# OpenBeacon.net
KiCad netlist of a schematic drawn in Altium Designer
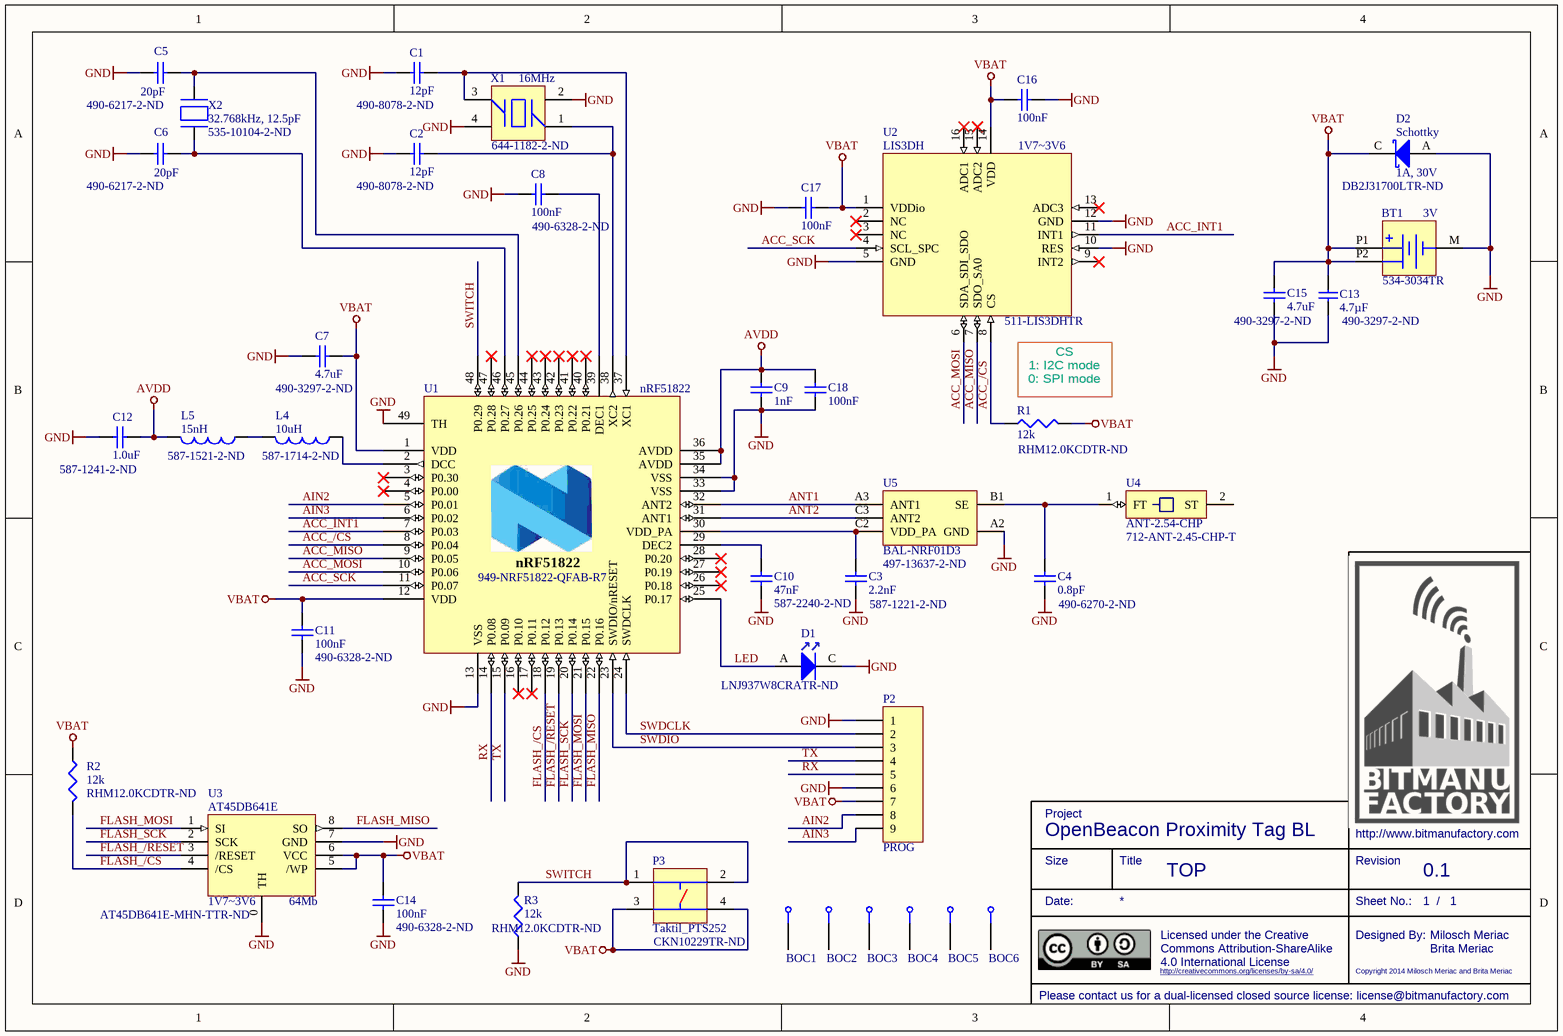
[diagram p0: OpenBeacon.SchDoc]

(export (version "E")
  (design (tool "Eeschema 10.0.6"))
  (components
    (comp (ref "BOC1")
      (value "Testpad")
      (footprint "TESTPAD_1MM")
      (libsource (lib "Bitmanufaktur") (part "Testpad"))
    )
    (comp (ref "BOC2")
      (value "Testpad")
      (footprint "TESTPAD_1MM")
      (libsource (lib "Bitmanufaktur") (part "Testpad"))
    )
    (comp (ref "BOC3")
      (value "Testpad")
      (footprint "TESTPAD_1MM")
      (libsource (lib "Bitmanufaktur") (part "Testpad"))
    )
    (comp (ref "BOC4")
      (value "Testpad")
      (footprint "TESTPAD_1MM")
      (libsource (lib "Bitmanufaktur") (part "Testpad"))
    )
    (comp (ref "BOC5")
      (value "Testpad")
      (footprint "TESTPAD_1MM")
      (libsource (lib "Bitmanufaktur") (part "Testpad"))
    )
    (comp (ref "BOC6")
      (value "Testpad")
      (footprint "TESTPAD_1MM")
      (libsource (lib "Bitmanufaktur") (part "Testpad"))
    )
    (comp (ref "BT1")
      (value "3V")
      (footprint "BAT-Holder_3034")
      (description "Battery Cell")
      (fields
        (field (name "SUPPLIER PART NUMBER 1") "534-3034TR")
        (field (name "Comment") "Battery Cell Holder")
      )
      (libsource (lib "Bitmanufaktur") (part "Battery_Cell"))
    )
    (comp (ref "C1")
      (value "12pF")
      (footprint "0402[1005]")
      (description "Capacitor (Semiconductor SIM Model)")
      (fields (field (name "TOLERANCE") "2%, NPO") (field (name "SUPPLIER PART NUMBER 1") "490-8078-2-ND"))
      (libsource (lib "Miscellaneous Devices") (part "Cap Semi"))
    )
    (comp (ref "C2")
      (value "12pF")
      (footprint "0402[1005]")
      (description "Capacitor (Semiconductor SIM Model)")
      (fields (field (name "TOLERANCE") "2%, NPO") (field (name "SUPPLIER PART NUMBER 1") "490-8078-2-ND"))
      (libsource (lib "Miscellaneous Devices") (part "Cap Semi"))
    )
    (comp (ref "C3")
      (value "2.2nF")
      (footprint "0402[1005]")
      (description "Capacitor (Semiconductor SIM Model)")
      (fields (field (name "TOLERANCE") "X7R, ±10%") (field (name "SUPPLIER PART NUMBER 1") "587-1221-2-ND"))
      (libsource (lib "Miscellaneous Devices") (part "Cap Semi"))
    )
    (comp (ref "C4")
      (value "0.8pF")
      (footprint "0402[1005]")
      (description "Capacitor (Semiconductor SIM Model)")
      (fields (field (name "TOLERANCE") "NP0, ±5%") (field (name "SUPPLIER PART NUMBER 1") "490-6270-2-ND"))
      (libsource (lib "Miscellaneous Devices") (part "Cap Semi"))
    )
    (comp (ref "C5")
      (value "20pF")
      (footprint "0402[1005]")
      (description "Capacitor (Semiconductor SIM Model)")
      (fields (field (name "SUPPLIER PART NUMBER 1") "490-6217-2-ND") (field (name "Comment") "Cap 20pF"))
      (libsource (lib "Bitmanufaktur") (part "Cap Semi"))
    )
    (comp (ref "C6")
      (value "20pF")
      (footprint "0402[1005]")
      (description "Capacitor (Semiconductor SIM Model)")
      (fields (field (name "SUPPLIER PART NUMBER 1") "490-6217-2-ND") (field (name "Comment") "Cap 20pF"))
      (libsource (lib "Bitmanufaktur") (part "Cap Semi"))
    )
    (comp (ref "C7")
      (value "4.7uF")
      (footprint "0603[1608]_a")
      (description "Capacitor (Semiconductor SIM Model)")
      (fields (field (name "TOLERANCE") "X5R, ±10%") (field (name "SUPPLIER PART NUMBER 1") "490-3297-2-ND"))
      (libsource (lib "Miscellaneous Devices") (part "Cap Semi"))
    )
    (comp (ref "C8")
      (value "100nF")
      (footprint "0402[1005]")
      (description "Capacitor (Semiconductor SIM Model)")
      (fields (field (name "TOLERANCE") "10%, X7R") (field (name "SUPPLIER PART NUMBER 1") "490-6328-2-ND"))
      (libsource (lib "Miscellaneous Devices") (part "Cap Semi"))
    )
    (comp (ref "C9")
      (value "1nF")
      (footprint "0402[1005]")
      (description "Capacitor (Semiconductor SIM Model)")
      (fields (field (name "TOLERANCE") "X7R, ±10%"))
      (libsource (lib "Miscellaneous Devices") (part "Cap Semi"))
    )
    (comp (ref "C10")
      (value "47nF")
      (footprint "0402[1005]")
      (description "Capacitor (Semiconductor SIM Model)")
      (fields (field (name "TOLERANCE") "X7R, ±10%") (field (name "SUPPLIER PART NUMBER 1") "587-2240-2-ND"))
      (libsource (lib "Miscellaneous Devices") (part "Cap Semi"))
    )
    (comp (ref "C11")
      (value "100nF")
      (footprint "0402[1005]")
      (description "Capacitor (Semiconductor SIM Model)")
      (fields (field (name "TOLERANCE") "10%, X7R") (field (name "SUPPLIER PART NUMBER 1") "490-6328-2-ND"))
      (libsource (lib "Miscellaneous Devices") (part "Cap Semi"))
    )
    (comp (ref "C12")
      (value "1.0uF")
      (footprint "0603[1608]_a")
      (description "Capacitor (Semiconductor SIM Model)")
      (fields (field (name "TOLERANCE") "10%, X7R") (field (name "SUPPLIER PART NUMBER 1") "587-1241-2-ND"))
      (libsource (lib "Miscellaneous Devices") (part "Cap Semi"))
    )
    (comp (ref "C13")
      (value "4.7µF")
      (footprint "0603[1608]_a")
      (description "Capacitor, X5R, ±10%")
      (fields
        (field (name "PART NUMBER") "C0603-4µ7")
        (field (name "SUPPLIER PART NUMBER 1") "490-3297-2-ND")
        (field (name "PUBLISHER") "Nordic Semiconductor")
      )
      (libsource (lib "Nordic Passive DB") (part "CAP"))
    )
    (comp (ref "C14")
      (value "100nF")
      (footprint "0402[1005]")
      (description "Capacitor (Semiconductor SIM Model)")
      (fields (field (name "TOLERANCE") "10%, X7R") (field (name "SUPPLIER PART NUMBER 1") "490-6328-2-ND"))
      (libsource (lib "Miscellaneous Devices") (part "Cap Semi"))
    )
    (comp (ref "C15")
      (value "4.7uF")
      (footprint "0603[1608]_a")
      (description "Capacitor (Semiconductor SIM Model)")
      (fields (field (name "TOLERANCE") "X5R, ±10%") (field (name "SUPPLIER PART NUMBER 1") "490-3297-2-ND"))
      (libsource (lib "Miscellaneous Devices") (part "Cap Semi"))
    )
    (comp (ref "C16")
      (value "100nF")
      (footprint "0402[1005]")
      (description "Capacitor (Semiconductor SIM Model)")
      (fields (field (name "TOLERANCE") "10%, X7R"))
      (libsource (lib "Miscellaneous Devices") (part "Cap Semi"))
    )
    (comp (ref "C17")
      (value "100nF")
      (footprint "0402[1005]")
      (description "Capacitor (Semiconductor SIM Model)")
      (fields (field (name "TOLERANCE") "10%, X7R"))
      (libsource (lib "Miscellaneous Devices") (part "Cap Semi"))
    )
    (comp (ref "C18")
      (value "100nF")
      (footprint "0402[1005]")
      (description "Capacitor (Semiconductor SIM Model)")
      (fields (field (name "TOLERANCE") "10%, X7R"))
      (libsource (lib "Miscellaneous Devices") (part "Cap Semi"))
    )
    (comp (ref "D1")
      (value "LED blue")
      (footprint "LED_0603")
      (description "LED")
      (fields (field (name "SUPPLIER PART NUMBER 1") "LNJ937W8CRATR-ND"))
      (libsource (lib "Bitmanufaktur") (part "LED"))
    )
    (comp (ref "D2")
      (value "Schottky")
      (footprint "SC-90A")
      (description "Schottky barrier diode")
      (fields
        (field (name "ALTIUM_VALUE") "1A, 30V")
        (field (name "SUPPLIER PART NUMBER 1") "DB2J31700LTR-ND")
      )
      (libsource (lib "Bitmanufaktur") (part "Diode_Shottky"))
    )
    (comp (ref "L4")
      (value "10uH")
      (footprint "0603[1608]_a")
      (description "Inductor / Spule")
      (fields (field (name "TOLERANCE") "10%") (field (name "SUPPLIER PART NUMBER 1") "587-1714-2-ND"))
      (libsource (lib "Bitmanufaktur") (part "COIL"))
    )
    (comp (ref "L5")
      (value "15nH")
      (footprint "0402[1005]")
      (description "Inductor / Spule")
      (fields (field (name "TOLERANCE") "5%") (field (name "SUPPLIER PART NUMBER 1") "587-1521-2-ND"))
      (libsource (lib "Bitmanufaktur") (part "COIL"))
    )
    (comp (ref "P2")
      (value "PROG")
      (footprint "HDR1X9_round_custom-SMD")
      (description "Header, 9-Pin")
      (libsource (lib "Miscellaneous Connectors") (part "Header 9"))
    )
    (comp (ref "P3")
      (value "Taktil_PTS252")
      (footprint "taktil_PTS525")
      (description "Taster")
      (fields (field (name "SUPPLIER PART NUMBER 1") "CKN10229TR-ND"))
      (libsource (lib "Bitmanufaktur") (part "Taktil_PTS252"))
    )
    (comp (ref "R1")
      (value "12k")
      (footprint "0402[1005]")
      (description "Resistor")
      (fields (field (name "TOLERANCE") "1%") (field (name "SUPPLIER PART NUMBER 1") "RHM12.0KCDTR-ND"))
      (libsource (lib "Bitmanufaktur") (part "Res"))
    )
    (comp (ref "R2")
      (value "12k")
      (footprint "0402[1005]")
      (description "Resistor")
      (fields (field (name "TOLERANCE") "1%") (field (name "SUPPLIER PART NUMBER 1") "RHM12.0KCDTR-ND"))
      (libsource (lib "Bitmanufaktur") (part "Res"))
    )
    (comp (ref "R3")
      (value "12k")
      (footprint "0402[1005]")
      (description "Resistor")
      (fields (field (name "TOLERANCE") "1%") (field (name "SUPPLIER PART NUMBER 1") "RHM12.0KCDTR-ND"))
      (libsource (lib "Bitmanufaktur") (part "Res"))
    )
    (comp (ref "U1")
      (value "nRF51822")
      (footprint "QFN-48")
      (fields (field (name "SUPPLIER PART NUMBER 1") "949-NRF51822-QFAB-R7"))
      (libsource (lib "Bitmanufaktur") (part "nRF51822"))
    )
    (comp (ref "U2")
      (value "LIS3DH")
      (footprint "LGA-16")
      (description "LIS3DH, MEMS digital output motion sensor")
      (fields
        (field (name "SUPPLY VOLTAGE") "1V7~3V6")
        (field (name "SUPPLIER PART NUMBER 1") "511-LIS3DHTR")
      )
      (libsource (lib "Bitmanufaktur") (part "LIS3DH"))
    )
    (comp (ref "U3")
      (value "AT45DB641E")
      (footprint "UDFN-8MA1")
      (description "serial interface Flash memory (1.7V-3.6V)")
      (fields
        (field (name "ALTIUM_VALUE") "64Mb")
        (field (name "SUPPLY VOLTAGE") "1V7~3V6")
        (field (name "SUPPLIER PART NUMBER 1") "AT45DB641E-MHN-TTR-ND")
      )
      (libsource (lib "Bitmanufaktur") (part "AT45DB641E"))
    )
    (comp (ref "U4")
      (value "ANT-2.54-CHP")
      (footprint "ANT-CHP_rainsun")
      (description "ANT-2.54-CHP, 2.45GHz Ultra-Compact Chip Antenna")
      (fields (field (name "SUPPLIER PART NUMBER 1") "712-ANT-2.45-CHP-T"))
      (libsource (lib "Bitmanufaktur") (part "ANT-CHP"))
    )
    (comp (ref "U5")
      (value "BAL-NRF01D3")
      (footprint "BAL-NRF01D3")
      (description "ST BAL-NRF01D31")
      (fields (field (name "SUPPLIER PART NUMBER 1") "497-13637-2-ND"))
      (libsource (lib "Bitmanufaktur") (part "BAL-NRF01D3"))
    )
    (comp (ref "X1")
      (value "16MHz")
      (footprint "SMD3225")
      (description "ABM8 ceramic crystal")
      (fields (field (name "SUPPLIER PART NUMBER 1") "644-1182-2-ND") (field (name "Comment") "XTAL_4Pin"))
      (libsource (lib "Bitmanufaktur") (part "XTAL_4Pin"))
    )
    (comp (ref "X2")
      (value "32.768kHz, 12.5pF")
      (footprint "ABS06")
      (description "Crystal")
      (fields (field (name "SUPPLIER PART NUMBER 1") "535-10104-2-ND") (field (name "Comment") "XTAL-2pin"))
      (libsource (lib "Bitmanufaktur") (part "XTAL_2Pin"))
    )
  )
  (nets
    (net (code "1") (name "/ACC_INT1") (class "Default")
      (node (ref "U1") (pin "7") (pinfunction "P0.03_7") (pintype "bidirectional"))
      (node (ref "U2") (pin "11") (pinfunction "INT1_11") (pintype "output"))
    )
    (net (code "2") (name "/ACC_MISO") (class "Default")
      (node (ref "U1") (pin "9") (pinfunction "P0.05_9") (pintype "bidirectional"))
      (node (ref "U2") (pin "7") (pinfunction "SDO_SA0_7") (pintype "bidirectional"))
    )
    (net (code "3") (name "/ACC_MOSI") (class "Default")
      (node (ref "U1") (pin "10") (pinfunction "P0.06_10") (pintype "bidirectional"))
      (node (ref "U2") (pin "6") (pinfunction "SDA_SDI_SDO_6") (pintype "bidirectional"))
    )
    (net (code "4") (name "/ACC_SCK") (class "Default")
      (node (ref "U1") (pin "11") (pinfunction "P0.07_11") (pintype "bidirectional"))
      (node (ref "U2") (pin "4") (pinfunction "SCL_SPC_4") (pintype "input"))
    )
    (net (code "5") (name "/ACC_{slash}CS") (class "Default")
      (node (ref "R1") (pin "1") (pinfunction "1_1") (pintype "passive"))
      (node (ref "U1") (pin "8") (pinfunction "P0.04_8") (pintype "bidirectional"))
      (node (ref "U2") (pin "8") (pinfunction "CS_8") (pintype "input"))
    )
    (net (code "6") (name "/AIN2") (class "Default")
      (node (ref "P2") (pin "8") (pinfunction "8_8") (pintype "passive"))
      (node (ref "U1") (pin "5") (pinfunction "P0.01_5") (pintype "bidirectional"))
    )
    (net (code "7") (name "/AIN3") (class "Default")
      (node (ref "P2") (pin "9") (pinfunction "9_9") (pintype "passive"))
      (node (ref "U1") (pin "6") (pinfunction "P0.02_6") (pintype "bidirectional"))
    )
    (net (code "8") (name "/ANT1") (class "Default")
      (node (ref "U1") (pin "32") (pinfunction "ANT2_32") (pintype "bidirectional"))
      (node (ref "U5") (pin "A3") (pinfunction "ANT1_A3") (pintype "passive"))
    )
    (net (code "9") (name "/ANT2") (class "Default")
      (node (ref "U1") (pin "31") (pinfunction "ANT1_31") (pintype "bidirectional"))
      (node (ref "U5") (pin "C3") (pinfunction "ANT2_C3") (pintype "passive"))
    )
    (net (code "10") (name "/FLASH_MISO") (class "Default")
      (node (ref "U1") (pin "22") (pinfunction "P0.16_22") (pintype "bidirectional"))
      (node (ref "U3") (pin "8") (pinfunction "SO_8") (pintype "output"))
    )
    (net (code "11") (name "/FLASH_MOSI") (class "Default")
      (node (ref "U1") (pin "21") (pinfunction "P0.15_21") (pintype "bidirectional"))
      (node (ref "U3") (pin "1") (pinfunction "SI_1") (pintype "input"))
    )
    (net (code "12") (name "/FLASH_SCK") (class "Default")
      (node (ref "U1") (pin "20") (pinfunction "P0.14_20") (pintype "bidirectional"))
      (node (ref "U3") (pin "2") (pinfunction "SCK_2") (pintype "passive"))
    )
    (net (code "13") (name "/FLASH_{slash}CS") (class "Default")
      (node (ref "R2") (pin "2") (pinfunction "2_2") (pintype "passive"))
      (node (ref "U1") (pin "18") (pinfunction "P0.12_18") (pintype "bidirectional"))
      (node (ref "U3") (pin "4") (pinfunction "/CS_4") (pintype "passive"))
    )
    (net (code "14") (name "/FLASH_{slash}RESET") (class "Default")
      (node (ref "U1") (pin "19") (pinfunction "P0.13_19") (pintype "bidirectional"))
      (node (ref "U3") (pin "3") (pinfunction "/RESET_3") (pintype "passive"))
    )
    (net (code "15") (name "/LED") (class "Default")
      (node (ref "D1") (pin "A") (pinfunction "Anode_A") (pintype "passive"))
      (node (ref "U1") (pin "25") (pinfunction "P0.17_25") (pintype "bidirectional"))
    )
    (net (code "16") (name "/RX") (class "Default")
      (node (ref "P2") (pin "5") (pinfunction "5_5") (pintype "passive"))
      (node (ref "U1") (pin "14") (pinfunction "P0.08_14") (pintype "bidirectional"))
    )
    (net (code "17") (name "/SWDCLK") (class "Default")
      (node (ref "P2") (pin "2") (pinfunction "2_2") (pintype "passive"))
      (node (ref "U1") (pin "24") (pinfunction "SWDCLK_24") (pintype "input"))
    )
    (net (code "18") (name "/SWDIO") (class "Default")
      (node (ref "P2") (pin "3") (pinfunction "3_3") (pintype "passive"))
      (node (ref "U1") (pin "23") (pinfunction "SWDIO/nRESET_23") (pintype "input"))
    )
    (net (code "19") (name "/SWITCH") (class "Default")
      (node (ref "P3") (pin "1") (pintype "passive"))
      (node (ref "P3") (pin "2") (pintype "passive"))
      (node (ref "R3") (pin "1") (pinfunction "1_1") (pintype "passive"))
      (node (ref "U1") (pin "48") (pinfunction "P0.29_48") (pintype "bidirectional"))
    )
    (net (code "20") (name "/TX") (class "Default")
      (node (ref "P2") (pin "4") (pinfunction "4_4") (pintype "passive"))
      (node (ref "U1") (pin "15") (pinfunction "P0.09_15") (pintype "bidirectional"))
    )
    (net (code "21") (name "AVDD") (class "Default")
      (node (ref "C12") (pin "1") (pinfunction "1_1") (pintype "passive"))
      (node (ref "C18") (pin "1") (pinfunction "1_1") (pintype "passive"))
      (node (ref "C9") (pin "1") (pinfunction "1_1") (pintype "passive"))
      (node (ref "L5") (pin "2") (pinfunction "2_2") (pintype "passive"))
      (node (ref "U1") (pin "35") (pinfunction "AVDD_35") (pintype "power_in"))
      (node (ref "U1") (pin "36") (pinfunction "AVDD_36") (pintype "power_in"))
    )
    (net (code "22") (name "GND") (class "Default")
      (node (ref "BT1") (pin "M") (pinfunction "M_M") (pintype "power_in"))
      (node (ref "C1") (pin "2") (pinfunction "2_2") (pintype "passive"))
      (node (ref "C10") (pin "2") (pinfunction "2_2") (pintype "passive"))
      (node (ref "C11") (pin "2") (pinfunction "2_2") (pintype "passive"))
      (node (ref "C12") (pin "2") (pinfunction "2_2") (pintype "passive"))
      (node (ref "C13") (pin "1") (pinfunction "1_1") (pintype "passive"))
      (node (ref "C14") (pin "2") (pinfunction "2_2") (pintype "passive"))
      (node (ref "C15") (pin "2") (pinfunction "2_2") (pintype "passive"))
      (node (ref "C16") (pin "1") (pinfunction "1_1") (pintype "passive"))
      (node (ref "C17") (pin "2") (pinfunction "2_2") (pintype "passive"))
      (node (ref "C18") (pin "2") (pinfunction "2_2") (pintype "passive"))
      (node (ref "C2") (pin "2") (pinfunction "2_2") (pintype "passive"))
      (node (ref "C3") (pin "2") (pinfunction "2_2") (pintype "passive"))
      (node (ref "C4") (pin "2") (pinfunction "2_2") (pintype "passive"))
      (node (ref "C5") (pin "1") (pinfunction "1_1") (pintype "passive"))
      (node (ref "C6") (pin "1") (pinfunction "1_1") (pintype "passive"))
      (node (ref "C7") (pin "2") (pinfunction "2_2") (pintype "passive"))
      (node (ref "C8") (pin "2") (pinfunction "2_2") (pintype "passive"))
      (node (ref "C9") (pin "2") (pinfunction "2_2") (pintype "passive"))
      (node (ref "D1") (pin "C") (pinfunction "Cathode_C") (pintype "passive"))
      (node (ref "D2") (pin "A") (pinfunction "Anode_A") (pintype "passive"))
      (node (ref "P2") (pin "1") (pinfunction "1_1") (pintype "passive"))
      (node (ref "P2") (pin "6") (pinfunction "6_6") (pintype "passive"))
      (node (ref "R3") (pin "2") (pinfunction "2_2") (pintype "passive"))
      (node (ref "U1") (pin "13") (pinfunction "VSS_13") (pintype "power_in"))
      (node (ref "U1") (pin "33") (pinfunction "VSS_33") (pintype "power_in"))
      (node (ref "U1") (pin "34") (pinfunction "VSS_34") (pintype "power_in"))
      (node (ref "U1") (pin "49") (pinfunction "TH_49") (pintype "passive"))
      (node (ref "U2") (pin "10") (pinfunction "RES_10") (pintype "input"))
      (node (ref "U2") (pin "12") (pinfunction "GND_12") (pintype "power_in"))
      (node (ref "U2") (pin "5") (pinfunction "GND_5") (pintype "power_in"))
      (node (ref "U3") (pin "0") (pinfunction "TH_0") (pintype "passive"))
      (node (ref "U3") (pin "7") (pinfunction "GND_7") (pintype "power_in"))
      (node (ref "U5") (pin "A2") (pinfunction "GND_A2") (pintype "passive"))
      (node (ref "X1") (pin "2") (pintype "passive"))
      (node (ref "X1") (pin "4") (pintype "passive"))
    )
    (net (code "23") (name "Net-(L4-Pad2)") (class "Default")
      (node (ref "L4") (pin "2") (pinfunction "2_2") (pintype "passive"))
      (node (ref "L5") (pin "1") (pinfunction "1_1") (pintype "passive"))
    )
    (net (code "24") (name "Net-(U1-DCC)") (class "Default")
      (node (ref "L4") (pin "1") (pinfunction "1_1") (pintype "passive"))
      (node (ref "U1") (pin "2") (pinfunction "DCC_2") (pintype "output"))
    )
    (net (code "25") (name "Net-(U1-DEC1)") (class "Default")
      (node (ref "C8") (pin "1") (pinfunction "1_1") (pintype "passive"))
      (node (ref "U1") (pin "39") (pinfunction "DEC1_39") (pintype "power_in"))
    )
    (net (code "26") (name "Net-(U1-DEC2)") (class "Default")
      (node (ref "C10") (pin "1") (pinfunction "1_1") (pintype "passive"))
      (node (ref "U1") (pin "29") (pinfunction "DEC2_29") (pintype "power_in"))
    )
    (net (code "27") (name "Net-(U1-P0.26)") (class "Default")
      (node (ref "C5") (pin "2") (pinfunction "2_2") (pintype "passive"))
      (node (ref "U1") (pin "45") (pinfunction "P0.26_45") (pintype "bidirectional"))
      (node (ref "X2") (pin "2") (pintype "passive"))
    )
    (net (code "28") (name "Net-(U1-P0.27)") (class "Default")
      (node (ref "C6") (pin "2") (pinfunction "2_2") (pintype "passive"))
      (node (ref "U1") (pin "46") (pinfunction "P0.27_46") (pintype "bidirectional"))
      (node (ref "X2") (pin "1") (pintype "passive"))
    )
    (net (code "29") (name "Net-(U1-VDD_PA)") (class "Default")
      (node (ref "C3") (pin "1") (pinfunction "1_1") (pintype "passive"))
      (node (ref "U1") (pin "30") (pinfunction "VDD_PA_30") (pintype "power_in"))
      (node (ref "U5") (pin "C2") (pinfunction "VDD_PA_C2") (pintype "passive"))
    )
    (net (code "30") (name "Net-(U1-XC1)") (class "Default")
      (node (ref "C1") (pin "1") (pinfunction "1_1") (pintype "passive"))
      (node (ref "U1") (pin "37") (pinfunction "XC1_37") (pintype "input"))
      (node (ref "X1") (pin "3") (pintype "passive"))
    )
    (net (code "31") (name "Net-(U1-XC2)") (class "Default")
      (node (ref "C2") (pin "1") (pinfunction "1_1") (pintype "passive"))
      (node (ref "U1") (pin "38") (pinfunction "XC2_38") (pintype "output"))
      (node (ref "X1") (pin "1") (pintype "passive"))
    )
    (net (code "32") (name "Net-(U4-FT)") (class "Default")
      (node (ref "C4") (pin "1") (pinfunction "1_1") (pintype "passive"))
      (node (ref "U4") (pin "1") (pinfunction "FT_1") (pintype "bidirectional"))
      (node (ref "U5") (pin "B1") (pinfunction "SE_B1") (pintype "passive"))
    )
    (net (code "33") (name "VBAT") (class "Default")
      (node (ref "BT1") (pin "P1") (pinfunction "P1_P1") (pintype "power_in"))
      (node (ref "BT1") (pin "P2") (pinfunction "P2_P2") (pintype "power_in"))
      (node (ref "C11") (pin "1") (pinfunction "1_1") (pintype "passive"))
      (node (ref "C13") (pin "2") (pinfunction "2_2") (pintype "passive"))
      (node (ref "C14") (pin "1") (pinfunction "1_1") (pintype "passive"))
      (node (ref "C15") (pin "1") (pinfunction "1_1") (pintype "passive"))
      (node (ref "C16") (pin "2") (pinfunction "2_2") (pintype "passive"))
      (node (ref "C17") (pin "1") (pinfunction "1_1") (pintype "passive"))
      (node (ref "C7") (pin "1") (pinfunction "1_1") (pintype "passive"))
      (node (ref "D2") (pin "C") (pinfunction "Cathode_C") (pintype "passive"))
      (node (ref "P2") (pin "7") (pinfunction "7_7") (pintype "passive"))
      (node (ref "P3") (pin "3") (pintype "passive"))
      (node (ref "P3") (pin "4") (pintype "passive"))
      (node (ref "R1") (pin "2") (pinfunction "2_2") (pintype "passive"))
      (node (ref "R2") (pin "1") (pinfunction "1_1") (pintype "passive"))
      (node (ref "U1") (pin "1") (pinfunction "VDD_1") (pintype "power_in"))
      (node (ref "U1") (pin "12") (pinfunction "VDD_12") (pintype "power_in"))
      (node (ref "U2") (pin "1") (pinfunction "VDDio_1") (pintype "power_in"))
      (node (ref "U2") (pin "14") (pinfunction "VDD_14") (pintype "power_in"))
      (node (ref "U3") (pin "5") (pinfunction "/WP_5") (pintype "passive"))
      (node (ref "U3") (pin "6") (pinfunction "VCC_6") (pintype "power_in"))
    )
    (net (code "34") (name "unconnected-(BOC1-Pad1)") (class "Default")
      (node (ref "BOC1") (pin "1") (pinfunction "1_1") (pintype "passive"))
    )
    (net (code "35") (name "unconnected-(BOC2-Pad1)") (class "Default")
      (node (ref "BOC2") (pin "1") (pinfunction "1_1") (pintype "passive"))
    )
    (net (code "36") (name "unconnected-(BOC3-Pad1)") (class "Default")
      (node (ref "BOC3") (pin "1") (pinfunction "1_1") (pintype "passive"))
    )
    (net (code "37") (name "unconnected-(BOC4-Pad1)") (class "Default")
      (node (ref "BOC4") (pin "1") (pinfunction "1_1") (pintype "passive"))
    )
    (net (code "38") (name "unconnected-(BOC5-Pad1)") (class "Default")
      (node (ref "BOC5") (pin "1") (pinfunction "1_1") (pintype "passive"))
    )
    (net (code "39") (name "unconnected-(BOC6-Pad1)") (class "Default")
      (node (ref "BOC6") (pin "1") (pinfunction "1_1") (pintype "passive"))
    )
    (net (code "40") (name "unconnected-(U1-P0.00-Pad4)") (class "Default")
      (node (ref "U1") (pin "4") (pinfunction "P0.00_4") (pintype "bidirectional+no_connect"))
    )
    (net (code "41") (name "unconnected-(U1-P0.10-Pad16)") (class "Default")
      (node (ref "U1") (pin "16") (pinfunction "P0.10_16") (pintype "bidirectional+no_connect"))
    )
    (net (code "42") (name "unconnected-(U1-P0.11-Pad17)") (class "Default")
      (node (ref "U1") (pin "17") (pinfunction "P0.11_17") (pintype "bidirectional+no_connect"))
    )
    (net (code "43") (name "unconnected-(U1-P0.18-Pad26)") (class "Default")
      (node (ref "U1") (pin "26") (pinfunction "P0.18_26") (pintype "bidirectional+no_connect"))
    )
    (net (code "44") (name "unconnected-(U1-P0.19-Pad27)") (class "Default")
      (node (ref "U1") (pin "27") (pinfunction "P0.19_27") (pintype "bidirectional+no_connect"))
    )
    (net (code "45") (name "unconnected-(U1-P0.20-Pad28)") (class "Default")
      (node (ref "U1") (pin "28") (pinfunction "P0.20_28") (pintype "bidirectional+no_connect"))
    )
    (net (code "46") (name "unconnected-(U1-P0.21-Pad40)") (class "Default")
      (node (ref "U1") (pin "40") (pinfunction "P0.21_40") (pintype "bidirectional+no_connect"))
    )
    (net (code "47") (name "unconnected-(U1-P0.22-Pad41)") (class "Default")
      (node (ref "U1") (pin "41") (pinfunction "P0.22_41") (pintype "bidirectional+no_connect"))
    )
    (net (code "48") (name "unconnected-(U1-P0.23-Pad42)") (class "Default")
      (node (ref "U1") (pin "42") (pinfunction "P0.23_42") (pintype "bidirectional+no_connect"))
    )
    (net (code "49") (name "unconnected-(U1-P0.24-Pad43)") (class "Default")
      (node (ref "U1") (pin "43") (pinfunction "P0.24_43") (pintype "bidirectional+no_connect"))
    )
    (net (code "50") (name "unconnected-(U1-P0.25-Pad44)") (class "Default")
      (node (ref "U1") (pin "44") (pinfunction "P0.25_44") (pintype "bidirectional+no_connect"))
    )
    (net (code "51") (name "unconnected-(U1-P0.28-Pad47)") (class "Default")
      (node (ref "U1") (pin "47") (pinfunction "P0.28_47") (pintype "bidirectional+no_connect"))
    )
    (net (code "52") (name "unconnected-(U1-P0.30-Pad3)") (class "Default")
      (node (ref "U1") (pin "3") (pinfunction "P0.30_3") (pintype "bidirectional+no_connect"))
    )
    (net (code "53") (name "unconnected-(U2-ADC1-Pad16)") (class "Default")
      (node (ref "U2") (pin "16") (pinfunction "ADC1_16") (pintype "input+no_connect"))
    )
    (net (code "54") (name "unconnected-(U2-ADC2-Pad15)") (class "Default")
      (node (ref "U2") (pin "15") (pinfunction "ADC2_15") (pintype "input+no_connect"))
    )
    (net (code "55") (name "unconnected-(U2-ADC3-Pad13)") (class "Default")
      (node (ref "U2") (pin "13") (pinfunction "ADC3_13") (pintype "input+no_connect"))
    )
    (net (code "56") (name "unconnected-(U2-INT2-Pad9)") (class "Default")
      (node (ref "U2") (pin "9") (pinfunction "INT2_9") (pintype "output+no_connect"))
    )
    (net (code "57") (name "unconnected-(U2-NC-Pad2)") (class "Default")
      (node (ref "U2") (pin "2") (pinfunction "NC_2") (pintype "passive+no_connect"))
    )
    (net (code "58") (name "unconnected-(U2-NC-Pad3)") (class "Default")
      (node (ref "U2") (pin "3") (pinfunction "NC_3") (pintype "passive+no_connect"))
    )
    (net (code "59") (name "unconnected-(U4-ST-Pad2)") (class "Default")
      (node (ref "U4") (pin "2") (pinfunction "ST_2") (pintype "passive"))
    )
  )
)
